# LightLog_SMD_0_6B.net
KiCad netlist of a schematic drawn in EAGLE
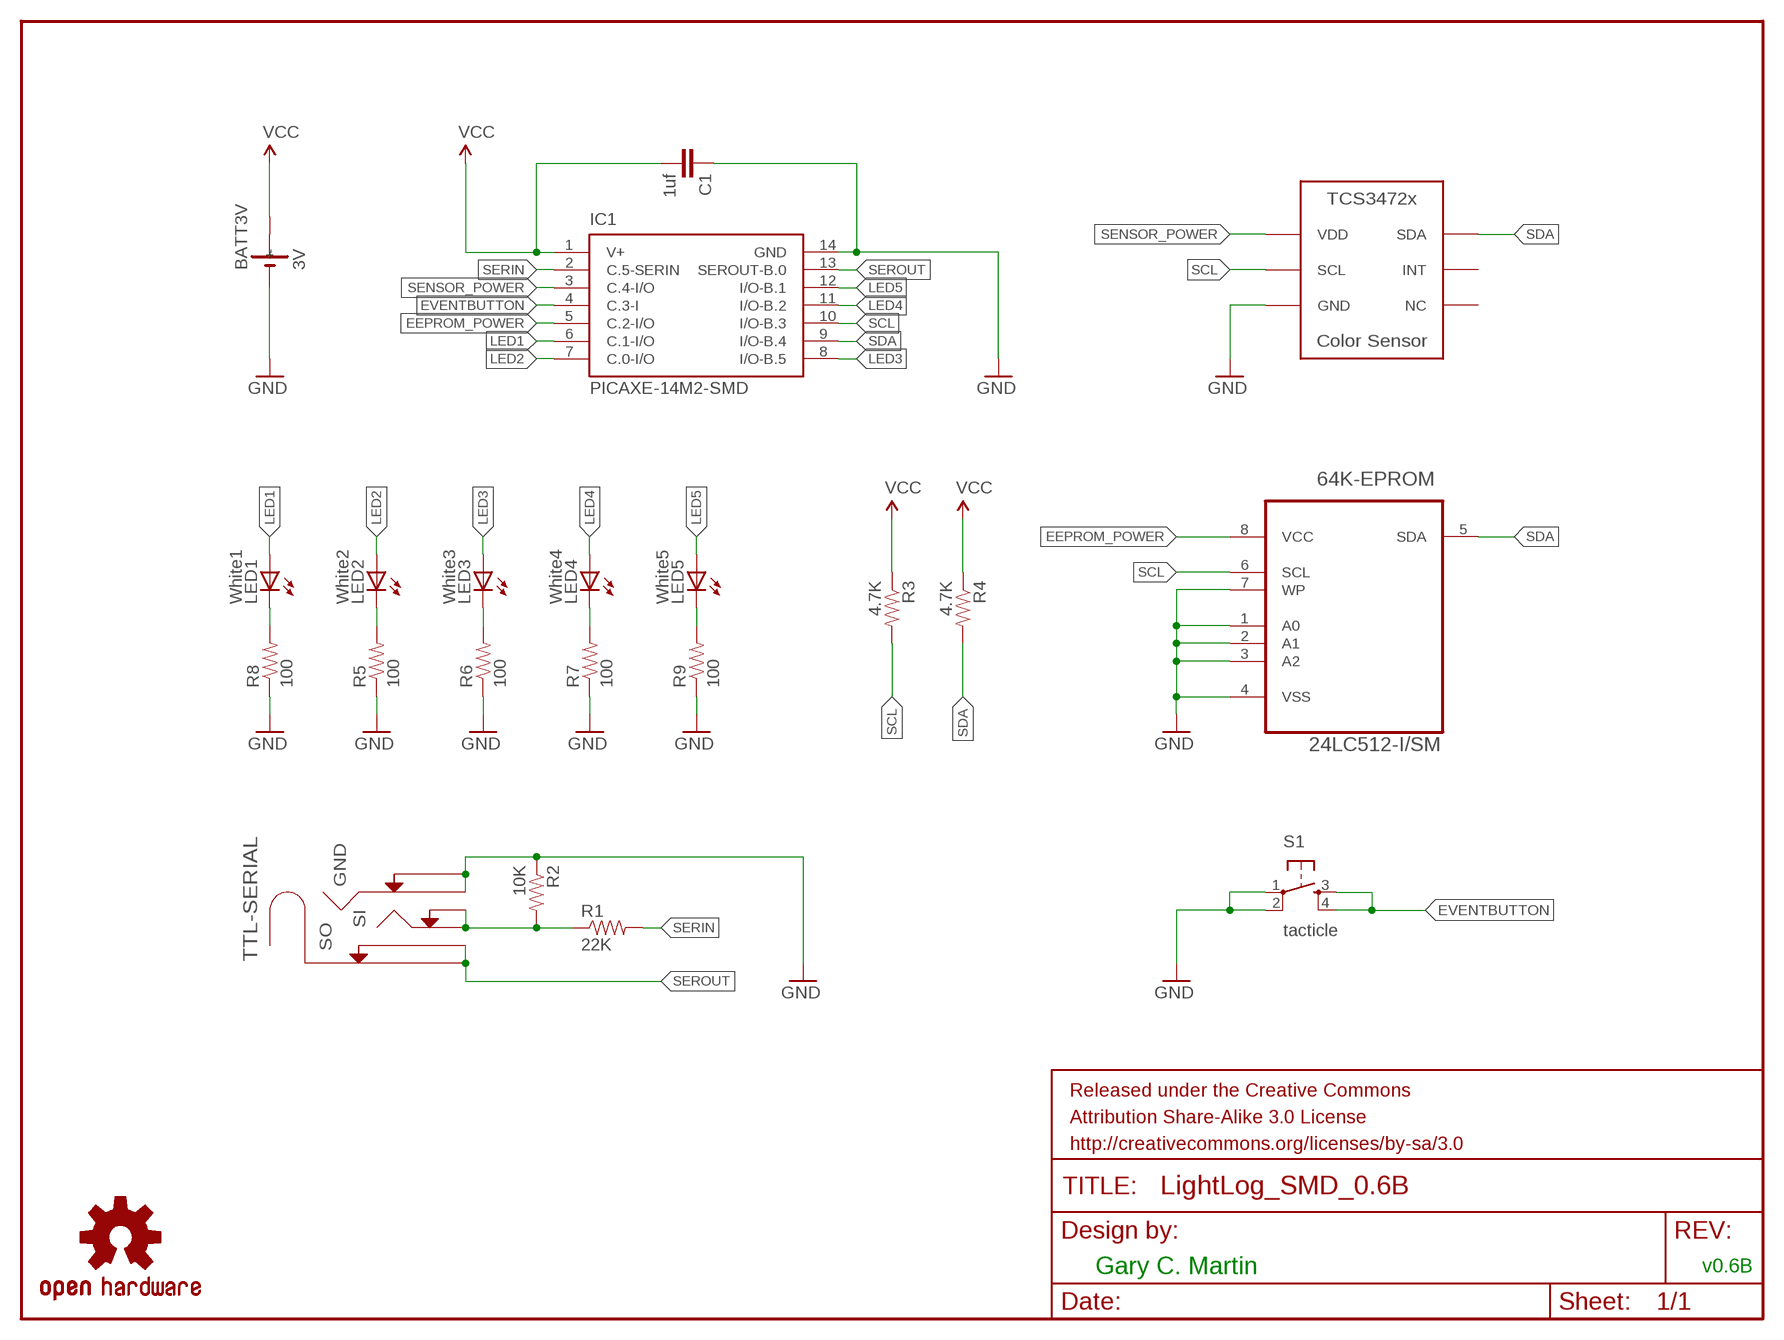
[diagram p0: schematic, sheet 1]

(export (version "E")
  (design (tool "Eeschema 10.0.6"))
  (components
    (comp (ref "64K-EPROM")
      (value "24LC512-I/SM")
      (footprint "eagle-import:SOIC127P794X203-8N")
      (libsource (lib "eagle-import") (part "24LC512-I/SM"))
    )
    (comp (ref "BATT3V")
      (value "3V")
      (footprint "eagle-import:BAT-HLD-001-CR2032-SMD")
      (libsource (lib "eagle-import") (part "BAT-HLD-001-CR2032"))
    )
    (comp (ref "C1")
      (value "1uf")
      (footprint "eagle-import:0805")
      (libsource (lib "eagle-import") (part "CAP0805"))
    )
    (comp (ref "IC1")
      (value "PICAXE-14M2-SMD")
      (footprint "eagle-import:SOIC14")
      (libsource (lib "eagle-import") (part "PICAXE-14M2-SMD"))
    )
    (comp (ref "LED1")
      (value "White1")
      (footprint "eagle-import:LED-1206")
      (libsource (lib "eagle-import") (part "LED1206"))
    )
    (comp (ref "LED2")
      (value "White2")
      (footprint "eagle-import:LED-1206")
      (libsource (lib "eagle-import") (part "LED1206"))
    )
    (comp (ref "LED3")
      (value "White3")
      (footprint "eagle-import:LED-1206")
      (libsource (lib "eagle-import") (part "LED1206"))
    )
    (comp (ref "LED4")
      (value "White4")
      (footprint "eagle-import:LED-1206")
      (libsource (lib "eagle-import") (part "LED1206"))
    )
    (comp (ref "LED5")
      (value "White5")
      (footprint "eagle-import:LED-1206")
      (libsource (lib "eagle-import") (part "LED1206"))
    )
    (comp (ref "LOGO1")
      (value "OSHW-LOGOS")
      (footprint "eagle-import:OSHW-LOGO-S")
      (libsource (lib "eagle-import") (part "OSHW-LOGOS"))
    )
    (comp (ref "R1")
      (value "22K")
      (footprint "eagle-import:0805")
      (libsource (lib "eagle-import") (part "RESISTOR0805-RES"))
    )
    (comp (ref "R2")
      (value "10K")
      (footprint "eagle-import:0805")
      (libsource (lib "eagle-import") (part "RESISTOR0805-RES"))
    )
    (comp (ref "R3")
      (value "4.7K")
      (footprint "eagle-import:0805")
      (libsource (lib "eagle-import") (part "RESISTOR0805-RES"))
    )
    (comp (ref "R4")
      (value "4.7K")
      (footprint "eagle-import:0805")
      (libsource (lib "eagle-import") (part "RESISTOR0805-RES"))
    )
    (comp (ref "R5")
      (value "100")
      (footprint "eagle-import:0805")
      (libsource (lib "eagle-import") (part "RESISTOR0805-RES"))
    )
    (comp (ref "R6")
      (value "100")
      (footprint "eagle-import:0805")
      (libsource (lib "eagle-import") (part "RESISTOR0805-RES"))
    )
    (comp (ref "R7")
      (value "100")
      (footprint "eagle-import:0805")
      (libsource (lib "eagle-import") (part "RESISTOR0805-RES"))
    )
    (comp (ref "R8")
      (value "100")
      (footprint "eagle-import:0805")
      (libsource (lib "eagle-import") (part "RESISTOR0805-RES"))
    )
    (comp (ref "R9")
      (value "100")
      (footprint "eagle-import:0805")
      (libsource (lib "eagle-import") (part "RESISTOR0805-RES"))
    )
    (comp (ref "S1")
      (value "tacticle")
      (footprint "eagle-import:TACTILE_SWITCH_SMD")
      (libsource (lib "eagle-import") (part "TAC_SWITCHSMD"))
    )
    (comp (ref "TTL-SERIAL")
      (value "3-5MM-STEREO-SOCKET")
      (footprint "eagle-import:3-5MM-SMT")
      (libsource (lib "eagle-import") (part "3-5MM-STEREO-SOCKET"))
    )
    (comp (ref "U$1")
      (value "TCS3472")
      (footprint "eagle-import:DUAL-FLAT-NO-LEAD-6PIN")
      (libsource (lib "eagle-import") (part "TCS3472"))
    )
  )
  (nets
    (net (code "1") (name "EEPROM_POWER") (class "Default")
      (node (ref "64K-EPROM") (pin "8") (pinfunction "VCC_8") (pintype "power_in"))
      (node (ref "IC1") (pin "5") (pinfunction "C.2-I/O_5") (pintype "bidirectional"))
    )
    (net (code "2") (name "EVENTBUTTON") (class "Default")
      (node (ref "IC1") (pin "4") (pinfunction "C.3-I_4") (pintype "input"))
      (node (ref "S1") (pin "3") (pinfunction "3_3") (pintype "passive"))
      (node (ref "S1") (pin "4") (pinfunction "4_4") (pintype "passive"))
    )
    (net (code "3") (name "GND") (class "Default")
      (node (ref "64K-EPROM") (pin "1") (pinfunction "A0_1") (pintype "input"))
      (node (ref "64K-EPROM") (pin "2") (pinfunction "A1_2") (pintype "input"))
      (node (ref "64K-EPROM") (pin "3") (pinfunction "A2_3") (pintype "input"))
      (node (ref "64K-EPROM") (pin "4") (pinfunction "VSS_4") (pintype "passive"))
      (node (ref "64K-EPROM") (pin "7") (pinfunction "WP_7") (pintype "input"))
      (node (ref "BATT3V") (pin "NEG") (pinfunction "-_NEG") (pintype "passive"))
      (node (ref "C1") (pin "1") (pinfunction "1_1") (pintype "passive"))
      (node (ref "IC1") (pin "14") (pinfunction "GND_14") (pintype "power_in"))
      (node (ref "R2") (pin "1") (pinfunction "1_1") (pintype "passive"))
      (node (ref "R5") (pin "1") (pinfunction "1_1") (pintype "passive"))
      (node (ref "R6") (pin "1") (pinfunction "1_1") (pintype "passive"))
      (node (ref "R7") (pin "1") (pinfunction "1_1") (pintype "passive"))
      (node (ref "R8") (pin "1") (pinfunction "1_1") (pintype "passive"))
      (node (ref "R9") (pin "1") (pinfunction "1_1") (pintype "passive"))
      (node (ref "S1") (pin "1") (pinfunction "1_1") (pintype "passive"))
      (node (ref "S1") (pin "2") (pinfunction "2_2") (pintype "passive"))
      (node (ref "TTL-SERIAL") (pin "5") (pinfunction "5_5") (pintype "bidirectional"))
      (node (ref "TTL-SERIAL") (pin "6") (pinfunction "6_6") (pintype "bidirectional"))
      (node (ref "U$1") (pin "3") (pinfunction "GND_3") (pintype "bidirectional"))
    )
    (net (code "4") (name "LED1") (class "Default")
      (node (ref "IC1") (pin "6") (pinfunction "C.1-I/O_6") (pintype "bidirectional"))
      (node (ref "LED1") (pin "A") (pinfunction "A_A") (pintype "passive"))
    )
    (net (code "5") (name "LED2") (class "Default")
      (node (ref "IC1") (pin "7") (pinfunction "C.0-I/O_7") (pintype "bidirectional"))
      (node (ref "LED2") (pin "A") (pinfunction "A_A") (pintype "passive"))
    )
    (net (code "6") (name "LED3") (class "Default")
      (node (ref "IC1") (pin "8") (pinfunction "I/O-B.5_8") (pintype "bidirectional"))
      (node (ref "LED3") (pin "A") (pinfunction "A_A") (pintype "passive"))
    )
    (net (code "7") (name "LED4") (class "Default")
      (node (ref "IC1") (pin "11") (pinfunction "I/O-B.2_11") (pintype "bidirectional"))
      (node (ref "LED4") (pin "A") (pinfunction "A_A") (pintype "passive"))
    )
    (net (code "8") (name "LED5") (class "Default")
      (node (ref "IC1") (pin "12") (pinfunction "I/O-B.1_12") (pintype "bidirectional"))
      (node (ref "LED5") (pin "A") (pinfunction "A_A") (pintype "passive"))
    )
    (net (code "9") (name "Net-(LED1-PadC)") (class "Default")
      (node (ref "LED1") (pin "C") (pinfunction "C_C") (pintype "passive"))
      (node (ref "R8") (pin "2") (pinfunction "2_2") (pintype "passive"))
    )
    (net (code "10") (name "Net-(LED2-PadC)") (class "Default")
      (node (ref "LED2") (pin "C") (pinfunction "C_C") (pintype "passive"))
      (node (ref "R5") (pin "2") (pinfunction "2_2") (pintype "passive"))
    )
    (net (code "11") (name "Net-(LED3-PadC)") (class "Default")
      (node (ref "LED3") (pin "C") (pinfunction "C_C") (pintype "passive"))
      (node (ref "R6") (pin "2") (pinfunction "2_2") (pintype "passive"))
    )
    (net (code "12") (name "Net-(LED4-PadC)") (class "Default")
      (node (ref "LED4") (pin "C") (pinfunction "C_C") (pintype "passive"))
      (node (ref "R7") (pin "2") (pinfunction "2_2") (pintype "passive"))
    )
    (net (code "13") (name "Net-(LED5-PadC)") (class "Default")
      (node (ref "LED5") (pin "C") (pinfunction "C_C") (pintype "passive"))
      (node (ref "R9") (pin "2") (pinfunction "2_2") (pintype "passive"))
    )
    (net (code "14") (name "Net-(R1-Pad1)") (class "Default")
      (node (ref "R1") (pin "1") (pinfunction "1_1") (pintype "passive"))
      (node (ref "R2") (pin "2") (pinfunction "2_2") (pintype "passive"))
      (node (ref "TTL-SERIAL") (pin "3") (pinfunction "3_3") (pintype "bidirectional"))
      (node (ref "TTL-SERIAL") (pin "4") (pinfunction "4_4") (pintype "bidirectional"))
    )
    (net (code "15") (name "SCL") (class "Default")
      (node (ref "64K-EPROM") (pin "6") (pinfunction "SCL_6") (pintype "input"))
      (node (ref "IC1") (pin "10") (pinfunction "I/O-B.3_10") (pintype "bidirectional"))
      (node (ref "R3") (pin "2") (pinfunction "2_2") (pintype "passive"))
      (node (ref "U$1") (pin "2") (pinfunction "SCL_2") (pintype "bidirectional"))
    )
    (net (code "16") (name "SDA") (class "Default")
      (node (ref "64K-EPROM") (pin "5") (pinfunction "SDA_5") (pintype "bidirectional"))
      (node (ref "IC1") (pin "9") (pinfunction "I/O-B.4_9") (pintype "bidirectional"))
      (node (ref "R4") (pin "2") (pinfunction "2_2") (pintype "passive"))
      (node (ref "U$1") (pin "6") (pinfunction "SDA_6") (pintype "bidirectional"))
    )
    (net (code "17") (name "SENSOR_POWER") (class "Default")
      (node (ref "IC1") (pin "3") (pinfunction "C.4-I/O_3") (pintype "bidirectional"))
      (node (ref "U$1") (pin "1") (pinfunction "VDD_1") (pintype "bidirectional"))
    )
    (net (code "18") (name "SERIN") (class "Default")
      (node (ref "IC1") (pin "2") (pinfunction "C.5-SERIN_2") (pintype "input"))
      (node (ref "R1") (pin "2") (pinfunction "2_2") (pintype "passive"))
    )
    (net (code "19") (name "SEROUT") (class "Default")
      (node (ref "IC1") (pin "13") (pinfunction "SEROUT-B.0_13") (pintype "output"))
      (node (ref "TTL-SERIAL") (pin "1") (pinfunction "1_1") (pintype "bidirectional"))
      (node (ref "TTL-SERIAL") (pin "2") (pinfunction "2_2") (pintype "bidirectional"))
    )
    (net (code "20") (name "VCC") (class "Default")
      (node (ref "BATT3V") (pin "POS1") (pinfunction "+_POS1") (pintype "passive"))
      (node (ref "C1") (pin "2") (pinfunction "2_2") (pintype "passive"))
      (node (ref "IC1") (pin "1") (pinfunction "V+_1") (pintype "power_in"))
      (node (ref "R3") (pin "1") (pinfunction "1_1") (pintype "passive"))
      (node (ref "R4") (pin "1") (pinfunction "1_1") (pintype "passive"))
    )
    (net (code "21") (name "unconnected-(BATT3V-+-PadPOS2)") (class "Default")
      (node (ref "BATT3V") (pin "POS2") (pinfunction "+_POS2") (pintype "passive"))
    )
    (net (code "22") (name "unconnected-(U$1-INT-Pad5)") (class "Default")
      (node (ref "U$1") (pin "5") (pinfunction "INT_5") (pintype "bidirectional"))
    )
    (net (code "23") (name "unconnected-(U$1-NC-Pad4)") (class "Default")
      (node (ref "U$1") (pin "4") (pinfunction "NC_4") (pintype "bidirectional"))
    )
  )
)
